# Power_Supply.net
KiCad netlist of a schematic drawn in Altium Designer
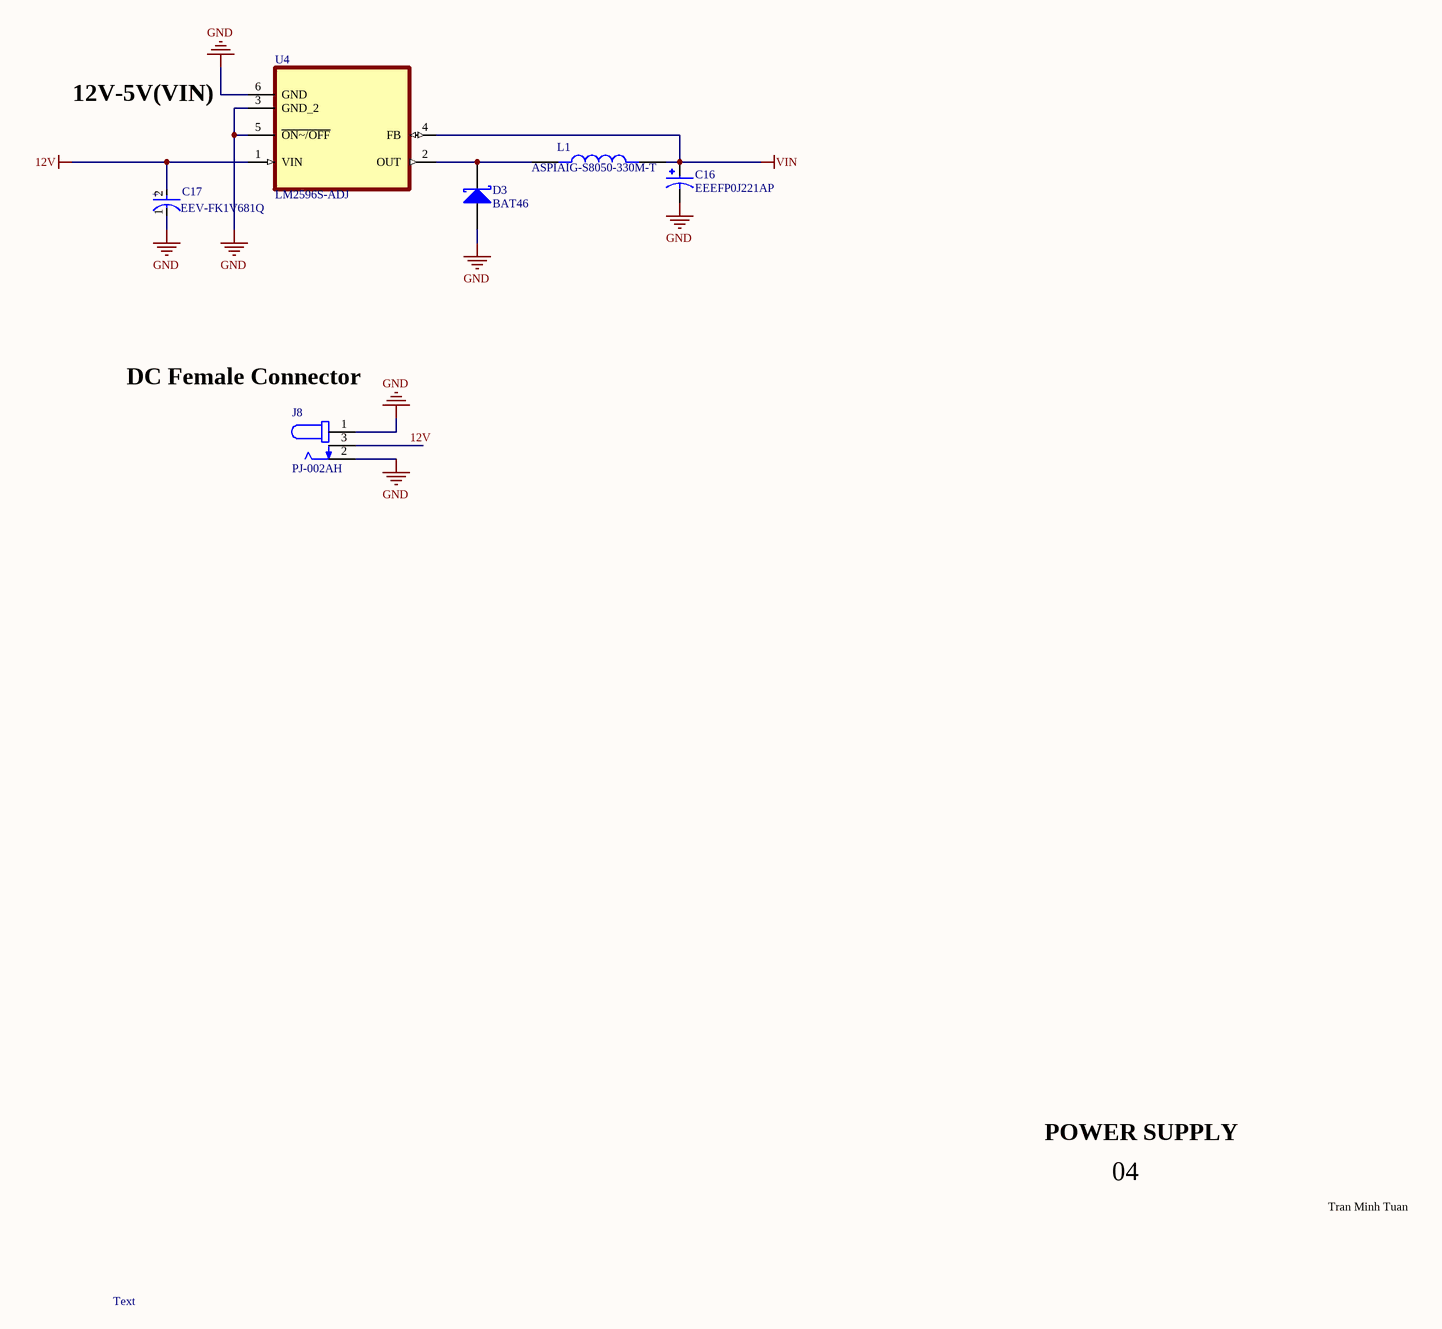
[diagram p0: Power Supply.SchDoc]

(export (version "E")
  (design (tool "Eeschema 10.0.6"))
  (components
    (comp (ref "C16")
      (value "EEEFP0J221AP")
      (footprint "CAP_EEEFP0J221AP")
      (description "CAP ALUM 220UF 20% 6.3V SMD")
      (fields (field (name "MF") "Panasonic"))
      (libsource (lib "220uF CAP") (part "EEEFP0J221AP"))
    )
    (comp (ref "C17")
      (value "EEV-FK1V681Q")
      (footprint "FP-FKH13-MFG")
      (description "CAP ALUM 680UF 20% 35V SMD")
      (fields (field (name "VOLTAGE") "35V") (field (name "TOLERANCE") "20%"))
      (libsource (lib "680uF capacitor") (part "CMP-05427-002172-1"))
    )
    (comp (ref "D3")
      (value "BAT46")
      (footprint "STM-DO-35-2")
      (description "Small Signal Schottky Diode, 150 mA, 100 V, -65 to 125 degC, 2-Pin DO-35, RoHS, Tape and Reel")
      (fields (field (name "MANUFACTURER") "STMicroelectronics"))
      (libsource (lib "Schottky diode") (part "CMP-2000-05926-1"))
    )
    (comp (ref "J8")
      (value "PJ-002AH")
      (footprint "CUI_PJ-002AH")
      (description "2.0 x 6.5 mm, 5.0 A, Horizontal, Through Hole, Dc Power Jack Connector")
      (fields (field (name "MF") "Same Sky"))
      (libsource (lib "DC connector") (part "PJ-002AH"))
    )
    (comp (ref "L1")
      (value "ASPIAIG-S8050-330M-T")
      (footprint "IND_ASPIAIG-S8050-330M-T")
      (description "Inductor Power Shielded Wirewound 33uH 20% 100KHz Ferrite 2A 122mOhm DCR 3131 Automotive T/R")
      (fields (field (name "MF") "Abracon LLC"))
      (libsource (lib "33uH indutor") (part "ASPIAIG-S8050-330M-T"))
    )
    (comp (ref "U4")
      (value "LM2596S-ADJ")
      (footprint "TO170P1435X465-6N")
      (fields (field (name "MF") "UMW"))
      (libsource (lib "LM2596S-ADJ") (part "LM2596S-ADJ"))
    )
  )
  (nets
    (net (code "1") (name "12V") (class "Default")
      (node (ref "C17") (pin "2") (pinfunction "A_2") (pintype "passive"))
      (node (ref "J8") (pin "3") (pinfunction "3_3") (pintype "passive"))
      (node (ref "U4") (pin "1") (pinfunction "VIN_1") (pintype "input"))
    )
    (net (code "2") (name "GND") (class "Default")
      (node (ref "C16") (pin "2") (pinfunction "2_2") (pintype "passive"))
      (node (ref "C17") (pin "1") (pinfunction "C_1") (pintype "passive"))
      (node (ref "D3") (pin "1") (pinfunction "A_1") (pintype "passive"))
      (node (ref "J8") (pin "1") (pinfunction "1_1") (pintype "passive"))
      (node (ref "J8") (pin "2") (pinfunction "2_2") (pintype "passive"))
      (node (ref "U4") (pin "3") (pinfunction "GND_2_3") (pintype "passive"))
      (node (ref "U4") (pin "5") (pinfunction "~{ON~/OFF}_5") (pintype "passive"))
      (node (ref "U4") (pin "6") (pinfunction "GND_6") (pintype "passive"))
    )
    (net (code "3") (name "Net-(D3-K)") (class "Default")
      (node (ref "D3") (pin "2") (pinfunction "K_2") (pintype "passive"))
      (node (ref "L1") (pin "1") (pinfunction "1_1") (pintype "passive"))
      (node (ref "U4") (pin "2") (pinfunction "OUT_2") (pintype "output"))
    )
    (net (code "4") (name "VIN") (class "Default")
      (node (ref "C16") (pin "1") (pinfunction "1_1") (pintype "passive"))
      (node (ref "L1") (pin "2") (pinfunction "2_2") (pintype "passive"))
      (node (ref "U4") (pin "4") (pinfunction "FB_4") (pintype "bidirectional"))
    )
  )
)
